# FPGA.net
KiCad netlist of a schematic drawn in Altium Designer
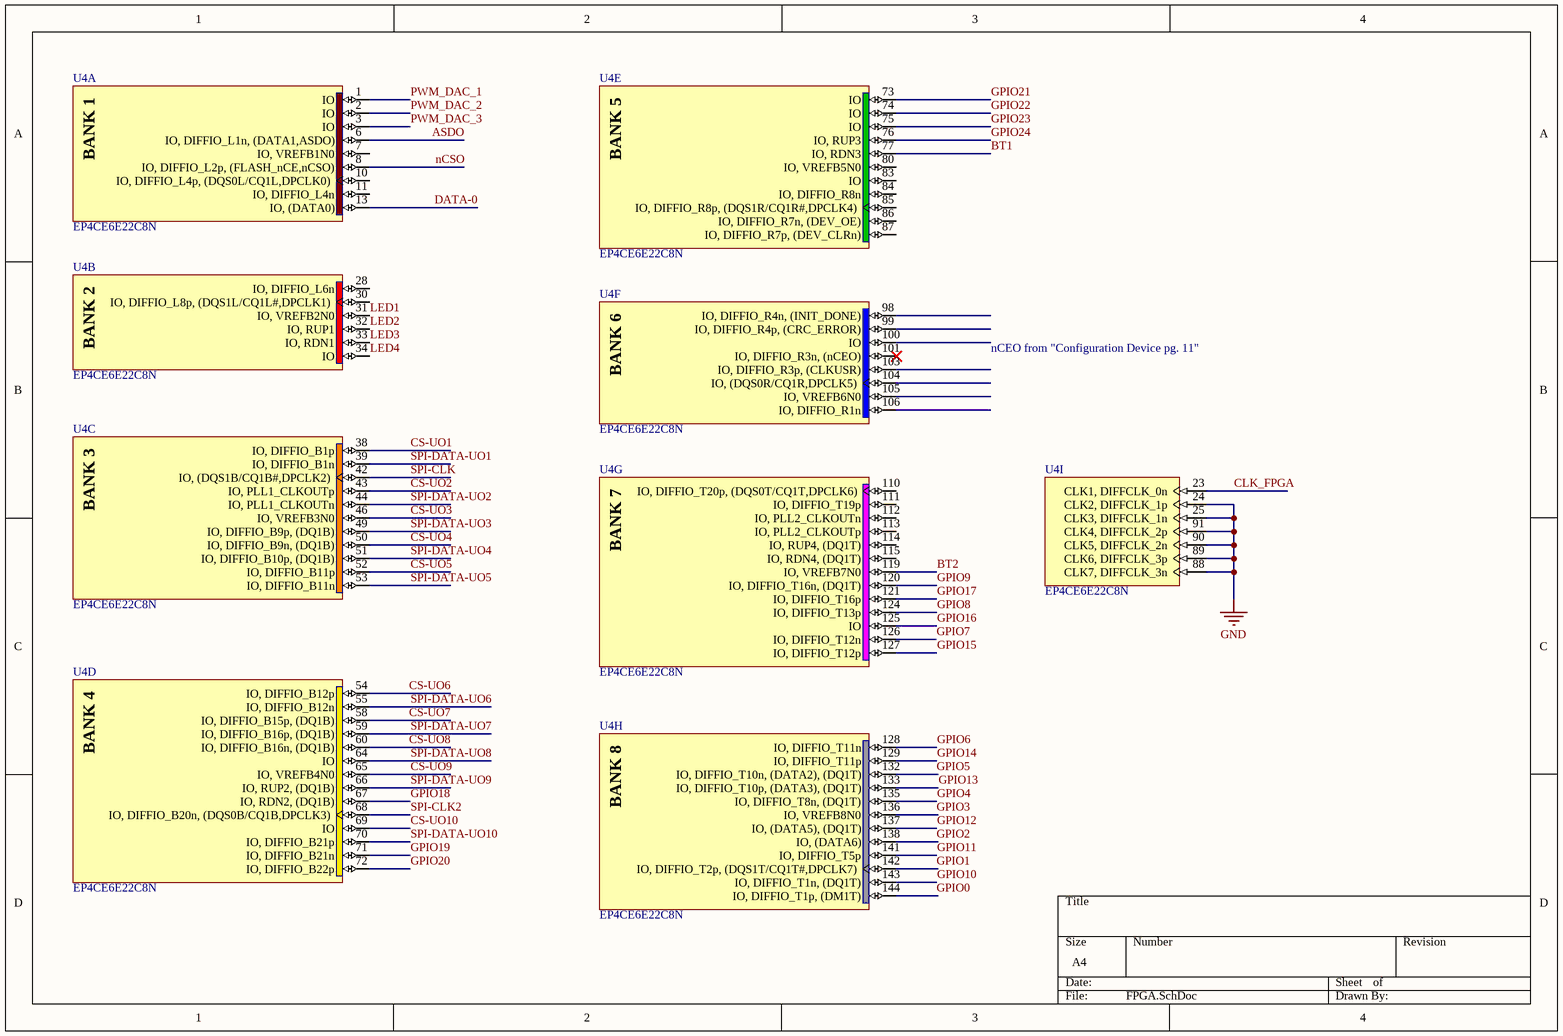
[diagram p0: FPGA.SchDoc]

(export (version "E")
  (design (tool "Eeschema 10.0.6"))
  (components
    (comp (ref "U4")
      (value "EP4CE6E22C8N")
      (footprint "EQFP144_M")
      (description "IC FPGA 91 I/O 144EQFP")
      (libsource (lib "Schlib1") (part "EP4CE6E22C8N"))
    )
  )
  (nets
    (net (code "1") (name "/ASDO") (class "Default")
      (node (ref "U4") (pin "6") (pinfunction "IO,_DIFFIO_L1n,_(DATA1,ASDO)_6") (pintype "bidirectional"))
    )
    (net (code "2") (name "/BT1") (class "Default")
      (node (ref "U4") (pin "77") (pinfunction "IO,_RDN3_77") (pintype "bidirectional"))
    )
    (net (code "3") (name "/BT2") (class "Default")
      (node (ref "U4") (pin "119") (pinfunction "IO,_VREFB7N0_119") (pintype "bidirectional"))
    )
    (net (code "4") (name "/CLK_FPGA") (class "Default")
      (node (ref "U4") (pin "23") (pinfunction "CLK1,_DIFFCLK_0n_23") (pintype "input"))
    )
    (net (code "5") (name "/CS-UO1") (class "Default")
      (node (ref "U4") (pin "38") (pinfunction "IO,_DIFFIO_B1p_38") (pintype "bidirectional"))
    )
    (net (code "6") (name "/CS-UO2") (class "Default")
      (node (ref "U4") (pin "43") (pinfunction "IO,_PLL1_CLKOUTp_43") (pintype "bidirectional"))
    )
    (net (code "7") (name "/CS-UO3") (class "Default")
      (node (ref "U4") (pin "46") (pinfunction "IO,_VREFB3N0_46") (pintype "bidirectional"))
    )
    (net (code "8") (name "/CS-UO4") (class "Default")
      (node (ref "U4") (pin "50") (pinfunction "IO,_DIFFIO_B9n,_(DQ1B)_50") (pintype "bidirectional"))
    )
    (net (code "9") (name "/CS-UO5") (class "Default")
      (node (ref "U4") (pin "52") (pinfunction "IO,_DIFFIO_B11p_52") (pintype "bidirectional"))
    )
    (net (code "10") (name "/CS-UO6") (class "Default")
      (node (ref "U4") (pin "54") (pinfunction "IO,_DIFFIO_B12p_54") (pintype "bidirectional"))
    )
    (net (code "11") (name "/CS-UO7") (class "Default")
      (node (ref "U4") (pin "58") (pinfunction "IO,_DIFFIO_B15p,_(DQ1B)_58") (pintype "bidirectional"))
    )
    (net (code "12") (name "/CS-UO8") (class "Default")
      (node (ref "U4") (pin "60") (pinfunction "IO,_DIFFIO_B16n,_(DQ1B)_60") (pintype "bidirectional"))
    )
    (net (code "13") (name "/CS-UO9") (class "Default")
      (node (ref "U4") (pin "65") (pinfunction "IO,_VREFB4N0_65") (pintype "bidirectional"))
    )
    (net (code "14") (name "/CS-UO10") (class "Default")
      (node (ref "U4") (pin "69") (pinfunction "IO_69") (pintype "bidirectional"))
    )
    (net (code "15") (name "/DATA-0") (class "Default")
      (node (ref "U4") (pin "13") (pinfunction "IO,_(DATA0)_13") (pintype "bidirectional"))
    )
    (net (code "16") (name "/GPIO0") (class "Default")
      (node (ref "U4") (pin "144") (pinfunction "IO,_DIFFIO_T1p,_(DM1T)_144") (pintype "bidirectional"))
    )
    (net (code "17") (name "/GPIO1") (class "Default")
      (node (ref "U4") (pin "142") (pinfunction "IO,_DIFFIO_T2p,_(DQS1T/CQ1T#,DPCLK7)_142") (pintype "bidirectional"))
    )
    (net (code "18") (name "/GPIO2") (class "Default")
      (node (ref "U4") (pin "138") (pinfunction "IO,_(DATA6)_138") (pintype "bidirectional"))
    )
    (net (code "19") (name "/GPIO3") (class "Default")
      (node (ref "U4") (pin "136") (pinfunction "IO,_VREFB8N0_136") (pintype "bidirectional"))
    )
    (net (code "20") (name "/GPIO4") (class "Default")
      (node (ref "U4") (pin "135") (pinfunction "IO,_DIFFIO_T8n,_(DQ1T)_135") (pintype "bidirectional"))
    )
    (net (code "21") (name "/GPIO5") (class "Default")
      (node (ref "U4") (pin "132") (pinfunction "IO,_DIFFIO_T10n,_(DATA2),_(DQ1T)_132") (pintype "bidirectional"))
    )
    (net (code "22") (name "/GPIO6") (class "Default")
      (node (ref "U4") (pin "128") (pinfunction "IO,_DIFFIO_T11n_128") (pintype "bidirectional"))
    )
    (net (code "23") (name "/GPIO7") (class "Default")
      (node (ref "U4") (pin "126") (pinfunction "IO,_DIFFIO_T12n_126") (pintype "bidirectional"))
    )
    (net (code "24") (name "/GPIO8") (class "Default")
      (node (ref "U4") (pin "124") (pinfunction "IO,_DIFFIO_T13p_124") (pintype "bidirectional"))
    )
    (net (code "25") (name "/GPIO9") (class "Default")
      (node (ref "U4") (pin "120") (pinfunction "IO,_DIFFIO_T16n,_(DQ1T)_120") (pintype "bidirectional"))
    )
    (net (code "26") (name "/GPIO10") (class "Default")
      (node (ref "U4") (pin "143") (pinfunction "IO,_DIFFIO_T1n,_(DQ1T)_143") (pintype "bidirectional"))
    )
    (net (code "27") (name "/GPIO11") (class "Default")
      (node (ref "U4") (pin "141") (pinfunction "IO,_DIFFIO_T5p_141") (pintype "bidirectional"))
    )
    (net (code "28") (name "/GPIO12") (class "Default")
      (node (ref "U4") (pin "137") (pinfunction "IO,_(DATA5),_(DQ1T)_137") (pintype "bidirectional"))
    )
    (net (code "29") (name "/GPIO13") (class "Default")
      (node (ref "U4") (pin "133") (pinfunction "IO,_DIFFIO_T10p,_(DATA3),_(DQ1T)_133") (pintype "bidirectional"))
    )
    (net (code "30") (name "/GPIO14") (class "Default")
      (node (ref "U4") (pin "129") (pinfunction "IO,_DIFFIO_T11p_129") (pintype "bidirectional"))
    )
    (net (code "31") (name "/GPIO15") (class "Default")
      (node (ref "U4") (pin "127") (pinfunction "IO,_DIFFIO_T12p_127") (pintype "bidirectional"))
    )
    (net (code "32") (name "/GPIO16") (class "Default")
      (node (ref "U4") (pin "125") (pinfunction "IO_125") (pintype "bidirectional"))
    )
    (net (code "33") (name "/GPIO17") (class "Default")
      (node (ref "U4") (pin "121") (pinfunction "IO,_DIFFIO_T16p_121") (pintype "bidirectional"))
    )
    (net (code "34") (name "/GPIO18") (class "Default")
      (node (ref "U4") (pin "67") (pinfunction "IO,_RDN2,_(DQ1B)_67") (pintype "bidirectional"))
    )
    (net (code "35") (name "/GPIO19") (class "Default")
      (node (ref "U4") (pin "71") (pinfunction "IO,_DIFFIO_B21n_71") (pintype "bidirectional"))
    )
    (net (code "36") (name "/GPIO20") (class "Default")
      (node (ref "U4") (pin "72") (pinfunction "IO,_DIFFIO_B22p_72") (pintype "bidirectional"))
    )
    (net (code "37") (name "/GPIO21") (class "Default")
      (node (ref "U4") (pin "73") (pinfunction "IO_73") (pintype "bidirectional"))
    )
    (net (code "38") (name "/GPIO22") (class "Default")
      (node (ref "U4") (pin "74") (pinfunction "IO_74") (pintype "bidirectional"))
    )
    (net (code "39") (name "/GPIO23") (class "Default")
      (node (ref "U4") (pin "75") (pinfunction "IO_75") (pintype "bidirectional"))
    )
    (net (code "40") (name "/GPIO24") (class "Default")
      (node (ref "U4") (pin "76") (pinfunction "IO,_RUP3_76") (pintype "bidirectional"))
    )
    (net (code "41") (name "/LED1") (class "Default")
      (node (ref "U4") (pin "31") (pinfunction "IO,_VREFB2N0_31") (pintype "bidirectional"))
    )
    (net (code "42") (name "/LED2") (class "Default")
      (node (ref "U4") (pin "32") (pinfunction "IO,_RUP1_32") (pintype "bidirectional"))
    )
    (net (code "43") (name "/LED3") (class "Default")
      (node (ref "U4") (pin "33") (pinfunction "IO,_RDN1_33") (pintype "bidirectional"))
    )
    (net (code "44") (name "/LED4") (class "Default")
      (node (ref "U4") (pin "34") (pinfunction "IO_34") (pintype "bidirectional"))
    )
    (net (code "45") (name "/PWM_DAC_1") (class "Default")
      (node (ref "U4") (pin "1") (pinfunction "IO_1") (pintype "bidirectional"))
    )
    (net (code "46") (name "/PWM_DAC_2") (class "Default")
      (node (ref "U4") (pin "2") (pinfunction "IO_2") (pintype "bidirectional"))
    )
    (net (code "47") (name "/PWM_DAC_3") (class "Default")
      (node (ref "U4") (pin "3") (pinfunction "IO_3") (pintype "bidirectional"))
    )
    (net (code "48") (name "/SPI-CLK") (class "Default")
      (node (ref "U4") (pin "42") (pinfunction "IO,_(DQS1B/CQ1B#,DPCLK2)_42") (pintype "bidirectional"))
    )
    (net (code "49") (name "/SPI-CLK2") (class "Default")
      (node (ref "U4") (pin "68") (pinfunction "IO,_DIFFIO_B20n,_(DQS0B/CQ1B,DPCLK3)_68") (pintype "bidirectional"))
    )
    (net (code "50") (name "/SPI-DATA-UO1") (class "Default")
      (node (ref "U4") (pin "39") (pinfunction "IO,_DIFFIO_B1n_39") (pintype "bidirectional"))
    )
    (net (code "51") (name "/SPI-DATA-UO2") (class "Default")
      (node (ref "U4") (pin "44") (pinfunction "IO,_PLL1_CLKOUTn_44") (pintype "bidirectional"))
    )
    (net (code "52") (name "/SPI-DATA-UO3") (class "Default")
      (node (ref "U4") (pin "49") (pinfunction "IO,_DIFFIO_B9p,_(DQ1B)_49") (pintype "bidirectional"))
    )
    (net (code "53") (name "/SPI-DATA-UO4") (class "Default")
      (node (ref "U4") (pin "51") (pinfunction "IO,_DIFFIO_B10p,_(DQ1B)_51") (pintype "bidirectional"))
    )
    (net (code "54") (name "/SPI-DATA-UO5") (class "Default")
      (node (ref "U4") (pin "53") (pinfunction "IO,_DIFFIO_B11n_53") (pintype "bidirectional"))
    )
    (net (code "55") (name "/SPI-DATA-UO6") (class "Default")
      (node (ref "U4") (pin "55") (pinfunction "IO,_DIFFIO_B12n_55") (pintype "bidirectional"))
    )
    (net (code "56") (name "/SPI-DATA-UO7") (class "Default")
      (node (ref "U4") (pin "59") (pinfunction "IO,_DIFFIO_B16p,_(DQ1B)_59") (pintype "bidirectional"))
    )
    (net (code "57") (name "/SPI-DATA-UO8") (class "Default")
      (node (ref "U4") (pin "64") (pinfunction "IO_64") (pintype "bidirectional"))
    )
    (net (code "58") (name "/SPI-DATA-UO9") (class "Default")
      (node (ref "U4") (pin "66") (pinfunction "IO,_RUP2,_(DQ1B)_66") (pintype "bidirectional"))
    )
    (net (code "59") (name "/SPI-DATA-UO10") (class "Default")
      (node (ref "U4") (pin "70") (pinfunction "IO,_DIFFIO_B21p_70") (pintype "bidirectional"))
    )
    (net (code "60") (name "/nCSO") (class "Default")
      (node (ref "U4") (pin "8") (pinfunction "IO,_DIFFIO_L2p,_(FLASH_nCE,nCSO)_8") (pintype "bidirectional"))
    )
    (net (code "61") (name "GND") (class "Default")
      (node (ref "U4") (pin "24") (pinfunction "CLK2,_DIFFCLK_1p_24") (pintype "input"))
      (node (ref "U4") (pin "25") (pinfunction "CLK3,_DIFFCLK_1n_25") (pintype "input"))
      (node (ref "U4") (pin "88") (pinfunction "CLK7,_DIFFCLK_3n_88") (pintype "input"))
      (node (ref "U4") (pin "89") (pinfunction "CLK6,_DIFFCLK_3p_89") (pintype "input"))
      (node (ref "U4") (pin "90") (pinfunction "CLK5,_DIFFCLK_2n_90") (pintype "input"))
      (node (ref "U4") (pin "91") (pinfunction "CLK4,_DIFFCLK_2p_91") (pintype "input"))
    )
    (net (code "62") (name "unconnected-(U4A-IO,_DIFFIO_L4n-Pad11)") (class "Default")
      (node (ref "U4") (pin "11") (pinfunction "IO,_DIFFIO_L4n_11") (pintype "bidirectional"))
    )
    (net (code "63") (name "unconnected-(U4A-IO,_DIFFIO_L4p,_(DQS0L{slash}CQ1L,DPCLK0)-Pad10)") (class "Default")
      (node (ref "U4") (pin "10") (pinfunction "IO,_DIFFIO_L4p,_(DQS0L/CQ1L,DPCLK0)_10") (pintype "bidirectional"))
    )
    (net (code "64") (name "unconnected-(U4A-IO,_VREFB1N0-Pad7)") (class "Default")
      (node (ref "U4") (pin "7") (pinfunction "IO,_VREFB1N0_7") (pintype "bidirectional"))
    )
    (net (code "65") (name "unconnected-(U4B-IO,_DIFFIO_L6n-Pad28)") (class "Default")
      (node (ref "U4") (pin "28") (pinfunction "IO,_DIFFIO_L6n_28") (pintype "bidirectional"))
    )
    (net (code "66") (name "unconnected-(U4B-IO,_DIFFIO_L8p,_(DQS1L{slash}CQ1L#,DPCLK1)-Pad30)") (class "Default")
      (node (ref "U4") (pin "30") (pinfunction "IO,_DIFFIO_L8p,_(DQS1L/CQ1L#,DPCLK1)_30") (pintype "bidirectional"))
    )
    (net (code "67") (name "unconnected-(U4E-IO,_DIFFIO_R7n,_(DEV_OE)-Pad86)") (class "Default")
      (node (ref "U4") (pin "86") (pinfunction "IO,_DIFFIO_R7n,_(DEV_OE)_86") (pintype "bidirectional"))
    )
    (net (code "68") (name "unconnected-(U4E-IO,_DIFFIO_R7p,_(DEV_CLRn)-Pad87)") (class "Default")
      (node (ref "U4") (pin "87") (pinfunction "IO,_DIFFIO_R7p,_(DEV_CLRn)_87") (pintype "bidirectional"))
    )
    (net (code "69") (name "unconnected-(U4E-IO,_DIFFIO_R8n-Pad84)") (class "Default")
      (node (ref "U4") (pin "84") (pinfunction "IO,_DIFFIO_R8n_84") (pintype "bidirectional"))
    )
    (net (code "70") (name "unconnected-(U4E-IO,_DIFFIO_R8p,_(DQS1R{slash}CQ1R#,DPCLK4)-Pad85)") (class "Default")
      (node (ref "U4") (pin "85") (pinfunction "IO,_DIFFIO_R8p,_(DQS1R/CQ1R#,DPCLK4)_85") (pintype "bidirectional"))
    )
    (net (code "71") (name "unconnected-(U4E-IO,_VREFB5N0-Pad80)") (class "Default")
      (node (ref "U4") (pin "80") (pinfunction "IO,_VREFB5N0_80") (pintype "bidirectional"))
    )
    (net (code "72") (name "unconnected-(U4E-IO-Pad83)") (class "Default")
      (node (ref "U4") (pin "83") (pinfunction "IO_83") (pintype "bidirectional"))
    )
    (net (code "73") (name "unconnected-(U4F-IO,_(DQS0R{slash}CQ1R,DPCLK5)-Pad104)") (class "Default")
      (node (ref "U4") (pin "104") (pinfunction "IO,_(DQS0R/CQ1R,DPCLK5)_104") (pintype "bidirectional"))
    )
    (net (code "74") (name "unconnected-(U4F-IO,_DIFFIO_R1n-Pad106)") (class "Default")
      (node (ref "U4") (pin "106") (pinfunction "IO,_DIFFIO_R1n_106") (pintype "bidirectional"))
    )
    (net (code "75") (name "unconnected-(U4F-IO,_DIFFIO_R3n,_(nCEO)-Pad101)") (class "Default")
      (node (ref "U4") (pin "101") (pinfunction "IO,_DIFFIO_R3n,_(nCEO)_101") (pintype "bidirectional+no_connect"))
    )
    (net (code "76") (name "unconnected-(U4F-IO,_DIFFIO_R3p,_(CLKUSR)-Pad103)") (class "Default")
      (node (ref "U4") (pin "103") (pinfunction "IO,_DIFFIO_R3p,_(CLKUSR)_103") (pintype "bidirectional"))
    )
    (net (code "77") (name "unconnected-(U4F-IO,_DIFFIO_R4n,_(INIT_DONE)-Pad98)") (class "Default")
      (node (ref "U4") (pin "98") (pinfunction "IO,_DIFFIO_R4n,_(INIT_DONE)_98") (pintype "bidirectional"))
    )
    (net (code "78") (name "unconnected-(U4F-IO,_DIFFIO_R4p,_(CRC_ERROR)-Pad99)") (class "Default")
      (node (ref "U4") (pin "99") (pinfunction "IO,_DIFFIO_R4p,_(CRC_ERROR)_99") (pintype "bidirectional"))
    )
    (net (code "79") (name "unconnected-(U4F-IO,_VREFB6N0-Pad105)") (class "Default")
      (node (ref "U4") (pin "105") (pinfunction "IO,_VREFB6N0_105") (pintype "bidirectional"))
    )
    (net (code "80") (name "unconnected-(U4F-IO-Pad100)") (class "Default")
      (node (ref "U4") (pin "100") (pinfunction "IO_100") (pintype "bidirectional"))
    )
    (net (code "81") (name "unconnected-(U4G-IO,_DIFFIO_T19p-Pad111)") (class "Default")
      (node (ref "U4") (pin "111") (pinfunction "IO,_DIFFIO_T19p_111") (pintype "bidirectional"))
    )
    (net (code "82") (name "unconnected-(U4G-IO,_DIFFIO_T20p,_(DQS0T{slash}CQ1T,DPCLK6)-Pad110)") (class "Default")
      (node (ref "U4") (pin "110") (pinfunction "IO,_DIFFIO_T20p,_(DQS0T/CQ1T,DPCLK6)_110") (pintype "bidirectional"))
    )
    (net (code "83") (name "unconnected-(U4G-IO,_PLL2_CLKOUTn-Pad112)") (class "Default")
      (node (ref "U4") (pin "112") (pinfunction "IO,_PLL2_CLKOUTn_112") (pintype "bidirectional"))
    )
    (net (code "84") (name "unconnected-(U4G-IO,_PLL2_CLKOUTp-Pad113)") (class "Default")
      (node (ref "U4") (pin "113") (pinfunction "IO,_PLL2_CLKOUTp_113") (pintype "bidirectional"))
    )
    (net (code "85") (name "unconnected-(U4G-IO,_RDN4,_(DQ1T)-Pad115)") (class "Default")
      (node (ref "U4") (pin "115") (pinfunction "IO,_RDN4,_(DQ1T)_115") (pintype "bidirectional"))
    )
    (net (code "86") (name "unconnected-(U4G-IO,_RUP4,_(DQ1T)-Pad114)") (class "Default")
      (node (ref "U4") (pin "114") (pinfunction "IO,_RUP4,_(DQ1T)_114") (pintype "bidirectional"))
    )
  )
)
